# Power_Conn.net
KiCad netlist of a schematic drawn in Altium Designer
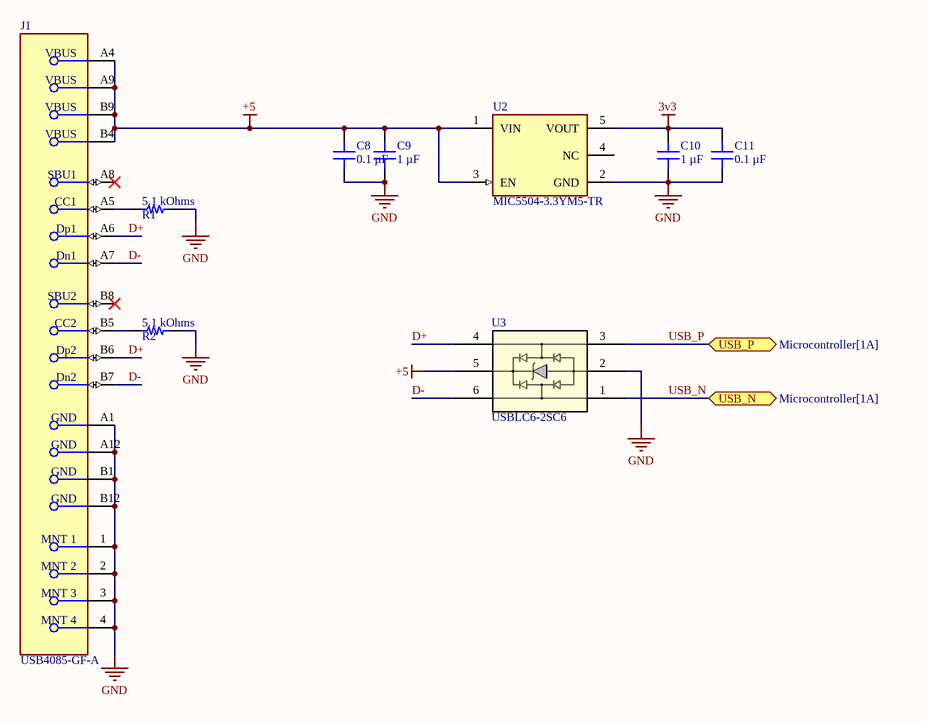
[diagram p0: Power_Conn.SchDoc]

(export (version "E")
  (design (tool "Eeschema 10.0.6"))
  (components
    (comp (ref "C8")
      (value "0.1 µF")
      (footprint "CAP 0603_1608")
      (description "CAP CER 0.1UF 50V X7R 0603")
      (fields
        (field (name "PART NUMBER") "CL10B104KB8NNNC")
        (field (name "MANUFACTURER") "Samsung Electro-Mechanics")
      )
      (libsource (lib "Celestial Altium Library - altium_library") (part "Capacitor"))
    )
    (comp (ref "C9")
      (value "1 µF")
      (footprint "CAP 0603_1608")
      (description "CAP CER 1UF 10V X7R 0603")
      (fields
        (field (name "PART NUMBER") "CL10B105KP8NFNC")
        (field (name "MANUFACTURER") "Samsung Electro-Mechanics")
      )
      (libsource (lib "Celestial Altium Library - altium_library") (part "Capacitor"))
    )
    (comp (ref "C10")
      (value "1 µF")
      (footprint "CAP 0603_1608")
      (description "CAP CER 1UF 10V X7R 0603")
      (fields
        (field (name "PART NUMBER") "CL10B105KP8NFNC")
        (field (name "MANUFACTURER") "Samsung Electro-Mechanics")
      )
      (libsource (lib "Celestial Altium Library - altium_library") (part "Capacitor"))
    )
    (comp (ref "C11")
      (value "0.1 µF")
      (footprint "CAP 0603_1608")
      (description "CAP CER 0.1UF 50V X7R 0603")
      (fields
        (field (name "PART NUMBER") "CL10B104KB8NNNC")
        (field (name "MANUFACTURER") "Samsung Electro-Mechanics")
      )
      (libsource (lib "Celestial Altium Library - altium_library") (part "Capacitor"))
    )
    (comp (ref "J1")
      (value "USB4085-GF-A")
      (footprint "FP-USB4085-GF-A-MFG")
      (description "CONN RCPT USB2.0 TYPE C 24POS RA")
      (libsource (lib "Altium Content Vault") (part "10fa745527c8b974685cbca3c197132"))
    )
    (comp (ref "R1")
      (value "5.1 kOhms")
      (footprint "RES 0805_2012")
      (description "RES 5.1K OHM 5% 1/8W 0805")
      (fields (field (name "PART NUMBER") "RC0805JR-075K1L") (field (name "MANUFACTURER") "Yageo"))
      (libsource (lib "Celestial Altium Library - altium_library") (part "Resistor"))
    )
    (comp (ref "R2")
      (value "5.1 kOhms")
      (footprint "RES 0805_2012")
      (description "RES 5.1K OHM 5% 1/8W 0805")
      (fields (field (name "PART NUMBER") "RC0805JR-075K1L") (field (name "MANUFACTURER") "Yageo"))
      (libsource (lib "Celestial Altium Library - altium_library") (part "Resistor"))
    )
    (comp (ref "U2")
      (value "MIC5504-3.3YM5-TR")
      (footprint "FP-SOT23-5LD-PL-1-MFG")
      (description "IC REG LINEAR 3.3V 300MA SOT23-5")
      (libsource (lib "Altium Content Vault") (part "96048095611b4a9579e1e315950d302"))
    )
    (comp (ref "U3")
      (value "USBLC6-2SC6")
      (footprint "SOT23-6L_STM")
      (description "No Description Available")
      (fields (field (name "COPYRIGHT") "Copyright (C) 2023 Ultra Librarian. All rights reserved."))
      (libsource (lib "2020-09-26_17-27-19") (part "USBLC6-2SC6"))
    )
  )
  (nets
    (net (code "1") (name "+5") (class "Default")
      (node (ref "C8") (pin "2") (pinfunction "2_2") (pintype "passive"))
      (node (ref "C9") (pin "2") (pinfunction "2_2") (pintype "passive"))
      (node (ref "J1") (pin "A4") (pinfunction "VBUS_A4") (pintype "power_in"))
      (node (ref "J1") (pin "A9") (pinfunction "VBUS_A9") (pintype "power_in"))
      (node (ref "J1") (pin "B4") (pinfunction "VBUS_B4") (pintype "power_in"))
      (node (ref "J1") (pin "B9") (pinfunction "VBUS_B9") (pintype "power_in"))
      (node (ref "U2") (pin "1") (pinfunction "VIN_1") (pintype "power_in"))
      (node (ref "U2") (pin "3") (pinfunction "EN_3") (pintype "input"))
      (node (ref "U3") (pin "5") (pinfunction "5_5") (pintype "passive"))
    )
    (net (code "2") (name "/D+") (class "Default")
      (node (ref "J1") (pin "A6") (pinfunction "Dp1_A6") (pintype "bidirectional"))
      (node (ref "J1") (pin "B6") (pinfunction "Dp2_B6") (pintype "bidirectional"))
      (node (ref "U3") (pin "4") (pinfunction "4_4") (pintype "passive"))
    )
    (net (code "3") (name "/D-") (class "Default")
      (node (ref "J1") (pin "A7") (pinfunction "Dn1_A7") (pintype "bidirectional"))
      (node (ref "J1") (pin "B7") (pinfunction "Dn2_B7") (pintype "bidirectional"))
      (node (ref "U3") (pin "6") (pinfunction "6_6") (pintype "passive"))
    )
    (net (code "4") (name "/USB_N") (class "Default")
      (node (ref "U3") (pin "1") (pinfunction "1_1") (pintype "passive"))
    )
    (net (code "5") (name "/USB_P") (class "Default")
      (node (ref "U3") (pin "3") (pinfunction "3_3") (pintype "passive"))
    )
    (net (code "6") (name "3v3") (class "Default")
      (node (ref "C10") (pin "2") (pinfunction "2_2") (pintype "passive"))
      (node (ref "C11") (pin "2") (pinfunction "2_2") (pintype "passive"))
      (node (ref "U2") (pin "5") (pinfunction "VOUT_5") (pintype "power_in"))
    )
    (net (code "7") (name "GND") (class "Default")
      (node (ref "C10") (pin "1") (pinfunction "1_1") (pintype "passive"))
      (node (ref "C11") (pin "1") (pinfunction "1_1") (pintype "passive"))
      (node (ref "C8") (pin "1") (pinfunction "1_1") (pintype "passive"))
      (node (ref "C9") (pin "1") (pinfunction "1_1") (pintype "passive"))
      (node (ref "J1") (pin "1") (pinfunction "MNT_1_1") (pintype "passive"))
      (node (ref "J1") (pin "2") (pinfunction "MNT_2_2") (pintype "passive"))
      (node (ref "J1") (pin "3") (pinfunction "MNT_3_3") (pintype "passive"))
      (node (ref "J1") (pin "4") (pinfunction "MNT_4_4") (pintype "passive"))
      (node (ref "J1") (pin "A1") (pinfunction "GND_A1") (pintype "power_in"))
      (node (ref "J1") (pin "A12") (pinfunction "GND_A12") (pintype "power_in"))
      (node (ref "J1") (pin "B1") (pinfunction "GND_B1") (pintype "power_in"))
      (node (ref "J1") (pin "B12") (pinfunction "GND_B12") (pintype "power_in"))
      (node (ref "R1") (pin "2") (pinfunction "2_2") (pintype "passive"))
      (node (ref "R2") (pin "2") (pinfunction "2_2") (pintype "passive"))
      (node (ref "U2") (pin "2") (pinfunction "GND_2") (pintype "power_in"))
      (node (ref "U3") (pin "2") (pinfunction "2_2") (pintype "passive"))
    )
    (net (code "8") (name "Net-(J1-CC1)") (class "Default")
      (node (ref "J1") (pin "A5") (pinfunction "CC1_A5") (pintype "bidirectional"))
      (node (ref "R1") (pin "1") (pinfunction "1_1") (pintype "passive"))
    )
    (net (code "9") (name "Net-(J1-CC2)") (class "Default")
      (node (ref "J1") (pin "B5") (pinfunction "CC2_B5") (pintype "bidirectional"))
      (node (ref "R2") (pin "1") (pinfunction "1_1") (pintype "passive"))
    )
    (net (code "10") (name "unconnected-(J1-SBU1-PadA8)") (class "Default")
      (node (ref "J1") (pin "A8") (pinfunction "SBU1_A8") (pintype "bidirectional+no_connect"))
    )
    (net (code "11") (name "unconnected-(J1-SBU2-PadB8)") (class "Default")
      (node (ref "J1") (pin "B8") (pinfunction "SBU2_B8") (pintype "bidirectional+no_connect"))
    )
    (net (code "12") (name "unconnected-(U2-NC-Pad4)") (class "Default")
      (node (ref "U2") (pin "4") (pinfunction "NC_4") (pintype "passive"))
    )
  )
)
